# RS485.net
KiCad netlist of a schematic drawn in Altium Designer
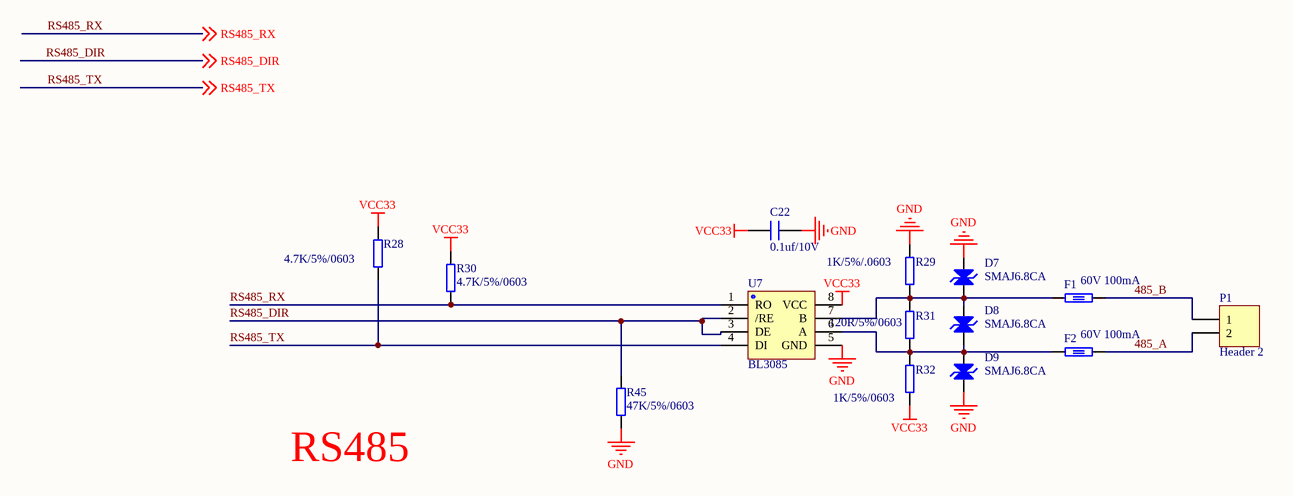
[diagram p0: RS485.SchDoc]

(export (version "E")
  (design (tool "Eeschema 10.0.6"))
  (components
    (comp (ref "C22") (value "0.1uf/10V") (footprint "0603R") (libsource (lib "ES_Schematic") (part "CAP")))
    (comp (ref "D7")
      (value "SMAJ6.8CA")
      (footprint "DO-214AC 双极性")
      (libsource (lib "ES_Schematic") (part "TVS"))
    )
    (comp (ref "D8")
      (value "SMAJ6.8CA")
      (footprint "DO-214AC 双极性")
      (libsource (lib "ES_Schematic") (part "TVS"))
    )
    (comp (ref "D9")
      (value "SMAJ6.8CA")
      (footprint "DO-214AC 双极性")
      (libsource (lib "ES_Schematic") (part "TVS"))
    )
    (comp (ref "F1") (value "60V 100mA") (footprint "R0603") (libsource (lib "sangjian") (part "FUSE")))
    (comp (ref "F2") (value "60V 100mA") (footprint "R0603") (libsource (lib "sangjian") (part "FUSE")))
    (comp (ref "P1")
      (value "Header 2")
      (footprint "CONN-TH_P5.08_KF127-5.08-2P")
      (description "Header, 2-Pin")
      (fields (field (name "PUBLISHER") "Altium Limited"))
      (libsource (lib "Miscellaneous Connectors") (part "Header 2"))
    )
    (comp (ref "R28")
      (value "4.7K/5%/0603")
      (footprint "0603R")
      (libsource (lib "ES_Schematic") (part "RES"))
    )
    (comp (ref "R29") (value "1K/5%/.0603") (footprint "0603R") (libsource (lib "ES_Schematic") (part "RES")))
    (comp (ref "R30")
      (value "4.7K/5%/0603")
      (footprint "0603R")
      (libsource (lib "ES_Schematic") (part "RES"))
    )
    (comp (ref "R31")
      (value "120R/5%/0603")
      (footprint "0603R")
      (libsource (lib "ES_Schematic") (part "RES"))
    )
    (comp (ref "R32") (value "1K/5%/0603") (footprint "0603R") (libsource (lib "ES_Schematic") (part "RES")))
    (comp (ref "R45") (value "47K/5%/0603") (footprint "0603R") (libsource (lib "ES_Schematic") (part "RES")))
    (comp (ref "U7") (value "BL3085") (footprint "SO8") (libsource (lib "ES_Schematic") (part "MAX485")))
  )
  (nets
    (net (code "1") (name "/485_A") (class "Default")
      (node (ref "F2") (pin "2") (pinfunction "2_2") (pintype "passive"))
      (node (ref "P1") (pin "2") (pinfunction "2_2") (pintype "passive"))
    )
    (net (code "2") (name "/485_B") (class "Default")
      (node (ref "F1") (pin "2") (pinfunction "2_2") (pintype "passive"))
      (node (ref "P1") (pin "1") (pinfunction "1_1") (pintype "passive"))
    )
    (net (code "3") (name "GND") (class "Default")
      (node (ref "C22") (pin "2") (pinfunction "2_2") (pintype "passive"))
      (node (ref "D7") (pin "1") (pinfunction "K_1") (pintype "passive"))
      (node (ref "D9") (pin "2") (pinfunction "A_2") (pintype "passive"))
      (node (ref "R29") (pin "1") (pinfunction "1_1") (pintype "passive"))
      (node (ref "R45") (pin "2") (pinfunction "2_2") (pintype "passive"))
      (node (ref "U7") (pin "5") (pinfunction "GND_5") (pintype "passive"))
    )
    (net (code "4") (name "Net-(D7-A)") (class "Default")
      (node (ref "D7") (pin "2") (pinfunction "A_2") (pintype "passive"))
      (node (ref "D8") (pin "1") (pinfunction "K_1") (pintype "passive"))
      (node (ref "F1") (pin "1") (pinfunction "1_1") (pintype "passive"))
      (node (ref "R29") (pin "2") (pinfunction "2_2") (pintype "passive"))
      (node (ref "R31") (pin "1") (pinfunction "1_1") (pintype "passive"))
      (node (ref "U7") (pin "7") (pinfunction "B_7") (pintype "passive"))
    )
    (net (code "5") (name "Net-(D8-A)") (class "Default")
      (node (ref "D8") (pin "2") (pinfunction "A_2") (pintype "passive"))
      (node (ref "D9") (pin "1") (pinfunction "K_1") (pintype "passive"))
      (node (ref "F2") (pin "1") (pinfunction "1_1") (pintype "passive"))
      (node (ref "R31") (pin "2") (pinfunction "2_2") (pintype "passive"))
      (node (ref "R32") (pin "1") (pinfunction "1_1") (pintype "passive"))
      (node (ref "U7") (pin "6") (pinfunction "A_6") (pintype "passive"))
    )
    (net (code "6") (name "RS485_DIR") (class "Default")
      (node (ref "R45") (pin "1") (pinfunction "1_1") (pintype "passive"))
      (node (ref "U7") (pin "2") (pinfunction "/RE_2") (pintype "passive"))
      (node (ref "U7") (pin "3") (pinfunction "DE_3") (pintype "passive"))
    )
    (net (code "7") (name "RS485_RX") (class "Default")
      (node (ref "R30") (pin "1") (pinfunction "1_1") (pintype "passive"))
      (node (ref "U7") (pin "1") (pinfunction "RO_1") (pintype "passive"))
    )
    (net (code "8") (name "RS485_TX") (class "Default")
      (node (ref "R28") (pin "1") (pinfunction "1_1") (pintype "passive"))
      (node (ref "U7") (pin "4") (pinfunction "DI_4") (pintype "passive"))
    )
    (net (code "9") (name "VCC33") (class "Default")
      (node (ref "C22") (pin "1") (pinfunction "1_1") (pintype "passive"))
      (node (ref "R28") (pin "2") (pinfunction "2_2") (pintype "passive"))
      (node (ref "R30") (pin "2") (pinfunction "2_2") (pintype "passive"))
      (node (ref "R32") (pin "2") (pinfunction "2_2") (pintype "passive"))
      (node (ref "U7") (pin "8") (pinfunction "VCC_8") (pintype "passive"))
    )
  )
)
